# SparkFun_GPS_NEO_M9N.net
KiCad netlist of a schematic drawn in EAGLE
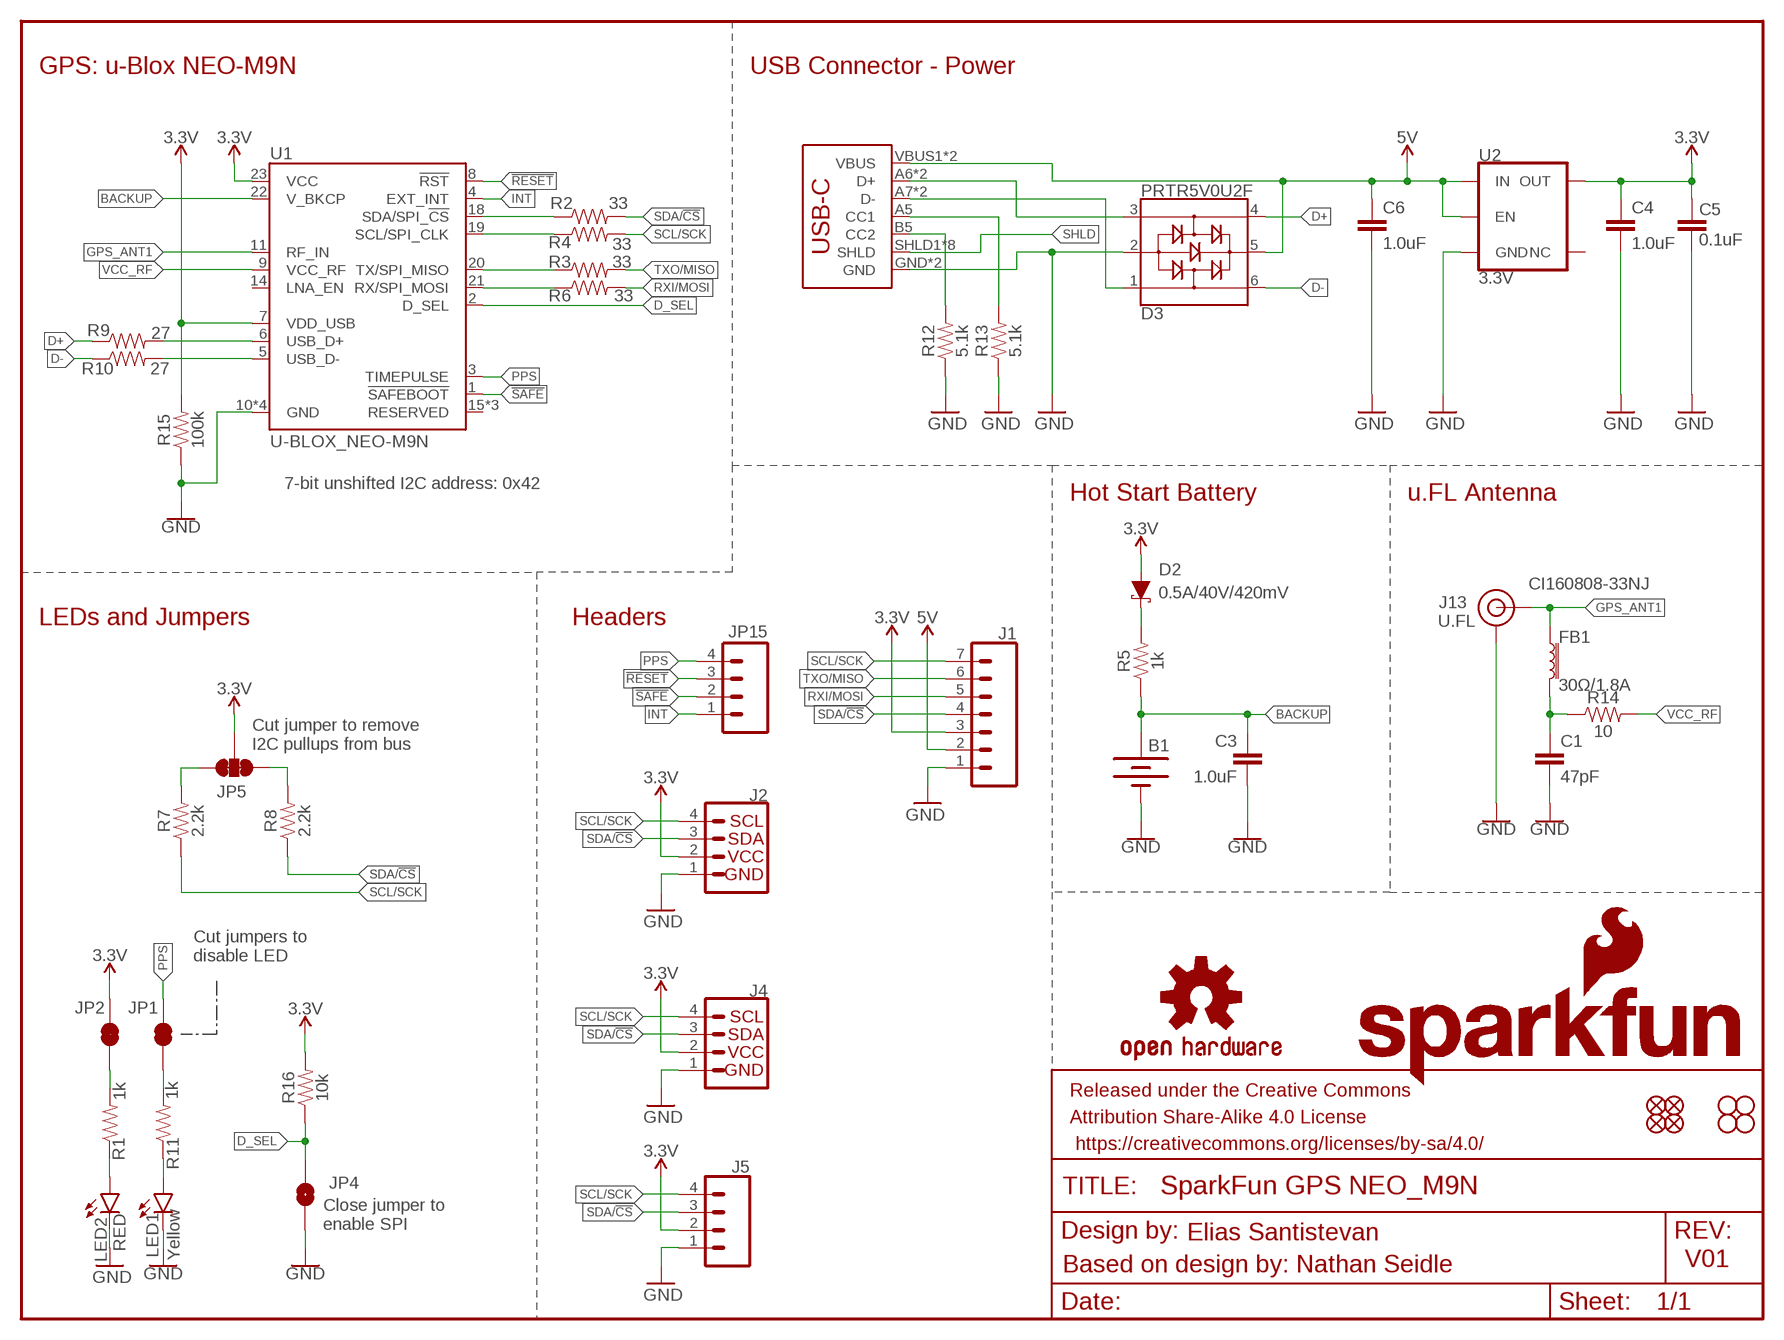
[diagram p0: schematic, sheet 1]

(export (version "E")
  (design (tool "Eeschema 10.0.6"))
  (components
    (comp (ref "B1")
      (value "6.8MM_COIN_CELL")
      (footprint "eagle-import:ML414H_IV01E")
      (libsource (lib "eagle-import") (part "ML414H_IV01E_BATTERY"))
    )
    (comp (ref "C1")
      (value "47pF")
      (footprint "eagle-import:0603")
      (libsource (lib "eagle-import") (part "47PF-0603-50V-5%"))
    )
    (comp (ref "C3")
      (value "1.0uF")
      (footprint "eagle-import:0603")
      (libsource (lib "eagle-import") (part "1.0UF-0603-16V-10%"))
    )
    (comp (ref "C4")
      (value "1.0uF")
      (footprint "eagle-import:0603")
      (libsource (lib "eagle-import") (part "1.0UF-0603-16V-10%"))
    )
    (comp (ref "C5")
      (value "0.1uF")
      (footprint "eagle-import:0603")
      (libsource (lib "eagle-import") (part "0.1UF-0603-25V-(+80/-20%)"))
    )
    (comp (ref "C6")
      (value "1.0uF")
      (footprint "eagle-import:0603")
      (libsource (lib "eagle-import") (part "1.0UF-0603-16V-10%"))
    )
    (comp (ref "D2")
      (value "0.5A/40V/420mV")
      (footprint "eagle-import:SOD-323")
      (libsource (lib "eagle-import") (part "DIODE-SCHOTTKY-PMEG4005EJ"))
    )
    (comp (ref "D3")
      (value "PRTR5V0U2F")
      (footprint "eagle-import:SOT886")
      (libsource (lib "eagle-import") (part "PRTR5V0U2F"))
    )
    (comp (ref "FB1")
      (value "30Ω/1.8A")
      (footprint "eagle-import:0603")
      (libsource (lib "eagle-import") (part "FERRITE_BEAD-0603"))
    )
    (comp (ref "FRAME1")
      (value "FRAME-LETTER")
      (footprint "eagle-import:CREATIVE_COMMONS")
      (libsource (lib "eagle-import") (part "FRAME-LETTER"))
    )
    (comp (ref "J1")
      (value "CONN_07NO_SILK")
      (footprint "eagle-import:1X07_NO_SILK")
      (libsource (lib "eagle-import") (part "CONN_07NO_SILK"))
    )
    (comp (ref "J2")
      (value "Qwiic Right Angle")
      (footprint "eagle-import:JST04_1MM_RA")
      (libsource (lib "eagle-import") (part "I2C_STANDARDQWIIC"))
    )
    (comp (ref "J3")
      (value "USB_C2-LAYER")
      (footprint "eagle-import:USB-C-16P")
      (libsource (lib "eagle-import") (part "USB_C2-LAYER"))
    )
    (comp (ref "J4")
      (value "Qwiic Right Angle")
      (footprint "eagle-import:JST04_1MM_RA")
      (libsource (lib "eagle-import") (part "I2C_STANDARDQWIIC"))
    )
    (comp (ref "J5")
      (value "CONN_041X04_NO_SILK")
      (footprint "eagle-import:1X04_NO_SILK")
      (libsource (lib "eagle-import") (part "CONN_041X04_NO_SILK"))
    )
    (comp (ref "J13")
      (value "U.FL")
      (footprint "eagle-import:U.FL")
      (libsource (lib "eagle-import") (part "U.FL2PIN"))
    )
    (comp (ref "JP1")
      (value "JUMPER-SMT_2_NC_TRACE_SILK")
      (footprint "eagle-import:SMT-JUMPER_2_NC_TRACE_SILK")
      (libsource (lib "eagle-import") (part "JUMPER-SMT_2_NC_TRACE_SILK"))
    )
    (comp (ref "JP2")
      (value "JUMPER-SMT_2_NC_TRACE_SILK")
      (footprint "eagle-import:SMT-JUMPER_2_NC_TRACE_SILK")
      (libsource (lib "eagle-import") (part "JUMPER-SMT_2_NC_TRACE_SILK"))
    )
    (comp (ref "JP4")
      (value "JUMPER-SMT_2_NO_SILK")
      (footprint "eagle-import:SMT-JUMPER_2_NO_SILK")
      (libsource (lib "eagle-import") (part "JUMPER-SMT_2_NO_SILK"))
    )
    (comp (ref "JP5")
      (value "JUMPER-SMT_3_2-NC_TRACE_SILK")
      (footprint "eagle-import:SMT-JUMPER_3_2-NC_TRACE_SILK")
      (libsource (lib "eagle-import") (part "JUMPER-SMT_3_2-NC_TRACE_SILK"))
    )
    (comp (ref "JP15")
      (value "CONN_041X04_NO_SILK")
      (footprint "eagle-import:1X04_NO_SILK")
      (libsource (lib "eagle-import") (part "CONN_041X04_NO_SILK"))
    )
    (comp (ref "JP21")
      (value "FIDUCIALUFIDUCIAL")
      (footprint "eagle-import:MICRO-FIDUCIAL")
      (libsource (lib "eagle-import") (part "FIDUCIALUFIDUCIAL"))
    )
    (comp (ref "JP31")
      (value "STAND-OFF")
      (footprint "eagle-import:STAND-OFF")
      (libsource (lib "eagle-import") (part "STAND-OFF"))
    )
    (comp (ref "JP41")
      (value "STAND-OFF")
      (footprint "eagle-import:STAND-OFF")
      (libsource (lib "eagle-import") (part "STAND-OFF"))
    )
    (comp (ref "JP61")
      (value "FIDUCIALUFIDUCIAL")
      (footprint "eagle-import:MICRO-FIDUCIAL")
      (libsource (lib "eagle-import") (part "FIDUCIALUFIDUCIAL"))
    )
    (comp (ref "JP71")
      (value "FIDUCIALUFIDUCIAL")
      (footprint "eagle-import:MICRO-FIDUCIAL")
      (libsource (lib "eagle-import") (part "FIDUCIALUFIDUCIAL"))
    )
    (comp (ref "JP81")
      (value "FIDUCIALUFIDUCIAL")
      (footprint "eagle-import:MICRO-FIDUCIAL")
      (libsource (lib "eagle-import") (part "FIDUCIALUFIDUCIAL"))
    )
    (comp (ref "JP91")
      (value "STAND-OFF")
      (footprint "eagle-import:STAND-OFF")
      (libsource (lib "eagle-import") (part "STAND-OFF"))
    )
    (comp (ref "JP101")
      (value "STAND-OFF")
      (footprint "eagle-import:STAND-OFF")
      (libsource (lib "eagle-import") (part "STAND-OFF"))
    )
    (comp (ref "LED1")
      (value "Yellow")
      (footprint "eagle-import:LED-0603")
      (libsource (lib "eagle-import") (part "LED-YELLOW0603"))
    )
    (comp (ref "LED2")
      (value "RED")
      (footprint "eagle-import:LED-0603")
      (libsource (lib "eagle-import") (part "LED-RED0603"))
    )
    (comp (ref "LOGO1")
      (value "OSHW-LOGOMINI")
      (footprint "eagle-import:OSHW-LOGO-MINI")
      (libsource (lib "eagle-import") (part "OSHW-LOGOMINI"))
    )
    (comp (ref "LOGO2")
      (value "SFE_LOGO_NAME_FLAME.1_INCH")
      (footprint "eagle-import:SFE_LOGO_NAME_FLAME_.1")
      (libsource (lib "eagle-import") (part "SFE_LOGO_NAME_FLAME.1_INCH"))
    )
    (comp (ref "R1")
      (value "1k")
      (footprint "eagle-import:0603")
      (libsource (lib "eagle-import") (part "1KOHM-0603-1/10W-1%"))
    )
    (comp (ref "R2")
      (value "33")
      (footprint "eagle-import:0603")
      (libsource (lib "eagle-import") (part "33OHM-0603-1/10W-1%"))
    )
    (comp (ref "R3")
      (value "33")
      (footprint "eagle-import:0603")
      (libsource (lib "eagle-import") (part "33OHM-0603-1/10W-1%"))
    )
    (comp (ref "R4")
      (value "33")
      (footprint "eagle-import:0603")
      (libsource (lib "eagle-import") (part "33OHM-0603-1/10W-1%"))
    )
    (comp (ref "R5")
      (value "1k")
      (footprint "eagle-import:0603")
      (libsource (lib "eagle-import") (part "1KOHM-0603-1/10W-1%"))
    )
    (comp (ref "R6")
      (value "33")
      (footprint "eagle-import:0603")
      (libsource (lib "eagle-import") (part "33OHM-0603-1/10W-1%"))
    )
    (comp (ref "R7")
      (value "2.2k")
      (footprint "eagle-import:0603")
      (libsource (lib "eagle-import") (part "2.2KOHM-0603-1/10W-1%"))
    )
    (comp (ref "R8")
      (value "2.2k")
      (footprint "eagle-import:0603")
      (libsource (lib "eagle-import") (part "2.2KOHM-0603-1/10W-1%"))
    )
    (comp (ref "R9")
      (value "27")
      (footprint "eagle-import:0603")
      (libsource (lib "eagle-import") (part "27OHM-0603-1/10W-1%"))
    )
    (comp (ref "R10")
      (value "27")
      (footprint "eagle-import:0603")
      (libsource (lib "eagle-import") (part "27OHM-0603-1/10W-1%"))
    )
    (comp (ref "R11")
      (value "1k")
      (footprint "eagle-import:0603")
      (libsource (lib "eagle-import") (part "1KOHM-0603-1/10W-1%"))
    )
    (comp (ref "R12")
      (value "5.1k")
      (footprint "eagle-import:0402")
      (libsource (lib "eagle-import") (part "5.1KOHM-0402-1/16W-1%"))
    )
    (comp (ref "R13")
      (value "5.1k")
      (footprint "eagle-import:0402")
      (libsource (lib "eagle-import") (part "5.1KOHM-0402-1/16W-1%"))
    )
    (comp (ref "R14")
      (value "10")
      (footprint "eagle-import:0603")
      (libsource (lib "eagle-import") (part "10OHM-0603-1/10W-1%"))
    )
    (comp (ref "R15")
      (value "100k")
      (footprint "eagle-import:0603")
      (libsource (lib "eagle-import") (part "100KOHM-0603-1/10W-1%"))
    )
    (comp (ref "R16")
      (value "10k")
      (footprint "eagle-import:0402")
      (libsource (lib "eagle-import") (part "10KOHM-0402-1/16W-1%"))
    )
    (comp (ref "U1")
      (value "U-BLOX_NEO-M9N")
      (footprint "eagle-import:NEO-M9N")
      (libsource (lib "eagle-import") (part "U-BLOX_NEO-M9N"))
    )
    (comp (ref "U2")
      (value "3.3V")
      (footprint "eagle-import:SOT23-5")
      (libsource (lib "eagle-import") (part "V_REG_AP2112K-3.3V"))
    )
  )
  (nets
    (net (code "1") (name "/SDA{slash}~{CS}") (class "Default")
      (node (ref "J1") (pin "4") (pinfunction "4_4") (pintype "passive"))
      (node (ref "J2") (pin "3") (pinfunction "3_3") (pintype "passive"))
      (node (ref "J4") (pin "3") (pinfunction "3_3") (pintype "passive"))
      (node (ref "J5") (pin "3") (pinfunction "3_3") (pintype "passive"))
      (node (ref "R2") (pin "2") (pinfunction "2_2") (pintype "passive"))
      (node (ref "R8") (pin "1") (pinfunction "1_1") (pintype "passive"))
    )
    (net (code "2") (name "/~{RESET}") (class "Default")
      (node (ref "JP15") (pin "3") (pinfunction "3_3") (pintype "passive"))
      (node (ref "U1") (pin "8") (pinfunction "~{RST}_8") (pintype "bidirectional"))
    )
    (net (code "3") (name "/~{SAFE}") (class "Default")
      (node (ref "JP15") (pin "2") (pinfunction "2_2") (pintype "passive"))
      (node (ref "U1") (pin "1") (pinfunction "~{SAFEBOOT}_1") (pintype "bidirectional"))
    )
    (net (code "4") (name "3.3V") (class "Default")
      (node (ref "C4") (pin "1") (pinfunction "1_1") (pintype "passive"))
      (node (ref "C5") (pin "2") (pinfunction "2_2") (pintype "passive"))
      (node (ref "D2") (pin "A") (pinfunction "A_A") (pintype "passive"))
      (node (ref "J1") (pin "3") (pinfunction "3_3") (pintype "passive"))
      (node (ref "J2") (pin "2") (pinfunction "2_2") (pintype "power_in"))
      (node (ref "J4") (pin "2") (pinfunction "2_2") (pintype "power_in"))
      (node (ref "J5") (pin "2") (pinfunction "2_2") (pintype "passive"))
      (node (ref "JP2") (pin "2") (pinfunction "2_2") (pintype "passive"))
      (node (ref "JP5") (pin "2") (pinfunction "2_2") (pintype "passive"))
      (node (ref "R15") (pin "2") (pinfunction "2_2") (pintype "passive"))
      (node (ref "R16") (pin "2") (pinfunction "2_2") (pintype "passive"))
      (node (ref "U1") (pin "23") (pinfunction "VCC_23") (pintype "bidirectional"))
      (node (ref "U1") (pin "7") (pinfunction "VDD_USB_7") (pintype "bidirectional"))
      (node (ref "U2") (pin "5") (pinfunction "OUT_5") (pintype "passive"))
    )
    (net (code "5") (name "5V") (class "Default")
      (node (ref "C6") (pin "1") (pinfunction "1_1") (pintype "passive"))
      (node (ref "D3") (pin "5") (pinfunction "5_5") (pintype "bidirectional"))
      (node (ref "J1") (pin "2") (pinfunction "2_2") (pintype "passive"))
      (node (ref "J3") (pin "VBUS1") (pinfunction "VBUS_VBUS1") (pintype "bidirectional"))
      (node (ref "J3") (pin "VBUS2") (pinfunction "VBUS_VBUS2") (pintype "bidirectional"))
      (node (ref "U2") (pin "1") (pinfunction "IN_1") (pintype "input"))
      (node (ref "U2") (pin "3") (pinfunction "EN_3") (pintype "input"))
    )
    (net (code "6") (name "BACKUP") (class "Default")
      (node (ref "B1") (pin "+") (pinfunction "+_+") (pintype "power_in"))
      (node (ref "C3") (pin "1") (pinfunction "1_1") (pintype "passive"))
      (node (ref "R5") (pin "1") (pinfunction "1_1") (pintype "passive"))
      (node (ref "U1") (pin "22") (pinfunction "V_BKCP_22") (pintype "bidirectional"))
    )
    (net (code "7") (name "D+") (class "Default")
      (node (ref "D3") (pin "4") (pinfunction "4_4") (pintype "bidirectional"))
      (node (ref "R9") (pin "1") (pinfunction "1_1") (pintype "passive"))
    )
    (net (code "8") (name "D-") (class "Default")
      (node (ref "D3") (pin "6") (pinfunction "6_6") (pintype "bidirectional"))
      (node (ref "R10") (pin "1") (pinfunction "1_1") (pintype "passive"))
    )
    (net (code "9") (name "D_SEL") (class "Default")
      (node (ref "JP4") (pin "2") (pinfunction "2_2") (pintype "passive"))
      (node (ref "R16") (pin "1") (pinfunction "1_1") (pintype "passive"))
      (node (ref "U1") (pin "2") (pinfunction "D_SEL_2") (pintype "bidirectional"))
    )
    (net (code "10") (name "GND") (class "Default")
      (node (ref "B1") (pin "-") (pinfunction "-_-") (pintype "power_in"))
      (node (ref "C1") (pin "2") (pinfunction "2_2") (pintype "passive"))
      (node (ref "C3") (pin "2") (pinfunction "2_2") (pintype "passive"))
      (node (ref "C4") (pin "2") (pinfunction "2_2") (pintype "passive"))
      (node (ref "C5") (pin "1") (pinfunction "1_1") (pintype "passive"))
      (node (ref "C6") (pin "2") (pinfunction "2_2") (pintype "passive"))
      (node (ref "D3") (pin "2") (pinfunction "2_2") (pintype "bidirectional"))
      (node (ref "J1") (pin "1") (pinfunction "1_1") (pintype "passive"))
      (node (ref "J13") (pin "1") (pinfunction "GND_1") (pintype "bidirectional"))
      (node (ref "J13") (pin "2") (pinfunction "GND_2") (pintype "bidirectional"))
      (node (ref "J2") (pin "1") (pinfunction "1_1") (pintype "power_in"))
      (node (ref "J3") (pin "GND") (pinfunction "GND_GND") (pintype "bidirectional"))
      (node (ref "J3") (pin "GND2") (pinfunction "GND_GND2") (pintype "bidirectional"))
      (node (ref "J4") (pin "1") (pinfunction "1_1") (pintype "power_in"))
      (node (ref "J5") (pin "1") (pinfunction "1_1") (pintype "passive"))
      (node (ref "JP4") (pin "1") (pinfunction "1_1") (pintype "passive"))
      (node (ref "LED1") (pin "C") (pinfunction "C_C") (pintype "passive"))
      (node (ref "LED2") (pin "C") (pinfunction "C_C") (pintype "passive"))
      (node (ref "R12") (pin "1") (pinfunction "1_1") (pintype "passive"))
      (node (ref "R13") (pin "1") (pinfunction "1_1") (pintype "passive"))
      (node (ref "R15") (pin "1") (pinfunction "1_1") (pintype "passive"))
      (node (ref "U1") (pin "10") (pinfunction "GND_10") (pintype "bidirectional"))
      (node (ref "U1") (pin "12") (pinfunction "GND_12") (pintype "bidirectional"))
      (node (ref "U1") (pin "13") (pinfunction "GND_13") (pintype "bidirectional"))
      (node (ref "U1") (pin "24") (pinfunction "GND_24") (pintype "bidirectional"))
      (node (ref "U2") (pin "2") (pinfunction "GND_2") (pintype "input"))
    )
    (net (code "11") (name "GPS_ANT1") (class "Default")
      (node (ref "FB1") (pin "1") (pinfunction "1_1") (pintype "passive"))
      (node (ref "J13") (pin "FEED") (pinfunction "SIGNAL_FEED") (pintype "bidirectional"))
      (node (ref "U1") (pin "11") (pinfunction "RF_IN_11") (pintype "bidirectional"))
    )
    (net (code "12") (name "INT") (class "Default")
      (node (ref "JP15") (pin "1") (pinfunction "1_1") (pintype "passive"))
      (node (ref "U1") (pin "4") (pinfunction "EXT_INT_4") (pintype "bidirectional"))
    )
    (net (code "13") (name "Net-(C1-Pad1)") (class "Default")
      (node (ref "C1") (pin "1") (pinfunction "1_1") (pintype "passive"))
      (node (ref "FB1") (pin "2") (pinfunction "2_2") (pintype "passive"))
      (node (ref "R14") (pin "1") (pinfunction "1_1") (pintype "passive"))
    )
    (net (code "14") (name "Net-(D2-PadC)") (class "Default")
      (node (ref "D2") (pin "C") (pinfunction "C_C") (pintype "passive"))
      (node (ref "R5") (pin "2") (pinfunction "2_2") (pintype "passive"))
    )
    (net (code "15") (name "Net-(D3-Pad1)") (class "Default")
      (node (ref "D3") (pin "1") (pinfunction "1_1") (pintype "bidirectional"))
      (node (ref "J3") (pin "A7") (pinfunction "D-_A7") (pintype "bidirectional"))
      (node (ref "J3") (pin "B7") (pinfunction "D-_B7") (pintype "bidirectional"))
    )
    (net (code "16") (name "Net-(D3-Pad3)") (class "Default")
      (node (ref "D3") (pin "3") (pinfunction "3_3") (pintype "bidirectional"))
      (node (ref "J3") (pin "A6") (pinfunction "D+_A6") (pintype "bidirectional"))
      (node (ref "J3") (pin "B6") (pinfunction "D+_B6") (pintype "bidirectional"))
    )
    (net (code "17") (name "Net-(J3-CC1)") (class "Default")
      (node (ref "J3") (pin "A5") (pinfunction "CC1_A5") (pintype "bidirectional"))
      (node (ref "R13") (pin "2") (pinfunction "2_2") (pintype "passive"))
    )
    (net (code "18") (name "Net-(J3-CC2)") (class "Default")
      (node (ref "J3") (pin "B5") (pinfunction "CC2_B5") (pintype "bidirectional"))
      (node (ref "R12") (pin "2") (pinfunction "2_2") (pintype "passive"))
    )
    (net (code "19") (name "Net-(JP1-Pad1)") (class "Default")
      (node (ref "JP1") (pin "1") (pinfunction "1_1") (pintype "passive"))
      (node (ref "R11") (pin "2") (pinfunction "2_2") (pintype "passive"))
    )
    (net (code "20") (name "Net-(JP2-Pad1)") (class "Default")
      (node (ref "JP2") (pin "1") (pinfunction "1_1") (pintype "passive"))
      (node (ref "R1") (pin "2") (pinfunction "2_2") (pintype "passive"))
    )
    (net (code "21") (name "Net-(JP5-Pad1)") (class "Default")
      (node (ref "JP5") (pin "1") (pinfunction "1_1") (pintype "passive"))
      (node (ref "R8") (pin "2") (pinfunction "2_2") (pintype "passive"))
    )
    (net (code "22") (name "Net-(JP5-Pad3)") (class "Default")
      (node (ref "JP5") (pin "3") (pinfunction "3_3") (pintype "passive"))
      (node (ref "R7") (pin "2") (pinfunction "2_2") (pintype "passive"))
    )
    (net (code "23") (name "Net-(LED1-PadA)") (class "Default")
      (node (ref "LED1") (pin "A") (pinfunction "A_A") (pintype "passive"))
      (node (ref "R11") (pin "1") (pinfunction "1_1") (pintype "passive"))
    )
    (net (code "24") (name "Net-(LED2-PadA)") (class "Default")
      (node (ref "LED2") (pin "A") (pinfunction "A_A") (pintype "passive"))
      (node (ref "R1") (pin "1") (pinfunction "1_1") (pintype "passive"))
    )
    (net (code "25") (name "Net-(U1-RX{slash}SPI_MOSI)") (class "Default")
      (node (ref "R6") (pin "1") (pinfunction "1_1") (pintype "passive"))
      (node (ref "U1") (pin "21") (pinfunction "RX/SPI_MOSI_21") (pintype "bidirectional"))
    )
    (net (code "26") (name "Net-(U1-SCL{slash}SPI_CLK)") (class "Default")
      (node (ref "R4") (pin "1") (pinfunction "1_1") (pintype "passive"))
      (node (ref "U1") (pin "19") (pinfunction "SCL/SPI_CLK_19") (pintype "bidirectional"))
    )
    (net (code "27") (name "Net-(U1-SDA{slash}SPI_~{CS})") (class "Default")
      (node (ref "R2") (pin "1") (pinfunction "1_1") (pintype "passive"))
      (node (ref "U1") (pin "18") (pinfunction "SDA/SPI_~{CS}_18") (pintype "bidirectional"))
    )
    (net (code "28") (name "Net-(U1-TX{slash}SPI_MISO)") (class "Default")
      (node (ref "R3") (pin "1") (pinfunction "1_1") (pintype "passive"))
      (node (ref "U1") (pin "20") (pinfunction "TX/SPI_MISO_20") (pintype "bidirectional"))
    )
    (net (code "29") (name "Net-(U1-USB_D+)") (class "Default")
      (node (ref "R9") (pin "2") (pinfunction "2_2") (pintype "passive"))
      (node (ref "U1") (pin "6") (pinfunction "USB_D+_6") (pintype "bidirectional"))
    )
    (net (code "30") (name "Net-(U1-USB_D-)") (class "Default")
      (node (ref "R10") (pin "2") (pinfunction "2_2") (pintype "passive"))
      (node (ref "U1") (pin "5") (pinfunction "USB_D-_5") (pintype "bidirectional"))
    )
    (net (code "31") (name "PPS") (class "Default")
      (node (ref "JP1") (pin "2") (pinfunction "2_2") (pintype "passive"))
      (node (ref "JP15") (pin "4") (pinfunction "4_4") (pintype "passive"))
      (node (ref "U1") (pin "3") (pinfunction "TIMEPULSE_3") (pintype "bidirectional"))
    )
    (net (code "32") (name "RXI{slash}MOSI") (class "Default")
      (node (ref "J1") (pin "5") (pinfunction "5_5") (pintype "passive"))
      (node (ref "R6") (pin "2") (pinfunction "2_2") (pintype "passive"))
    )
    (net (code "33") (name "SCL{slash}SCK") (class "Default")
      (node (ref "J1") (pin "7") (pinfunction "7_7") (pintype "passive"))
      (node (ref "J2") (pin "4") (pinfunction "4_4") (pintype "passive"))
      (node (ref "J4") (pin "4") (pinfunction "4_4") (pintype "passive"))
      (node (ref "J5") (pin "4") (pinfunction "4_4") (pintype "passive"))
      (node (ref "R4") (pin "2") (pinfunction "2_2") (pintype "passive"))
      (node (ref "R7") (pin "1") (pinfunction "1_1") (pintype "passive"))
    )
    (net (code "34") (name "SHLD") (class "Default")
      (node (ref "J3") (pin "SHLD1") (pinfunction "SHLD_SHLD1") (pintype "bidirectional"))
      (node (ref "J3") (pin "SHLD2") (pinfunction "SHLD_SHLD2") (pintype "bidirectional"))
      (node (ref "J3") (pin "SHLD3") (pinfunction "SHLD_SHLD3") (pintype "bidirectional"))
      (node (ref "J3") (pin "SHLD4") (pinfunction "SHLD_SHLD4") (pintype "bidirectional"))
      (node (ref "J3") (pin "SHLD5") (pinfunction "SHLD_SHLD5") (pintype "bidirectional"))
      (node (ref "J3") (pin "SHLD6") (pinfunction "SHLD_SHLD6") (pintype "bidirectional"))
      (node (ref "J3") (pin "SHLD7") (pinfunction "SHLD_SHLD7") (pintype "bidirectional"))
      (node (ref "J3") (pin "SHLD8") (pinfunction "SHLD_SHLD8") (pintype "bidirectional"))
    )
    (net (code "35") (name "TXO{slash}MISO") (class "Default")
      (node (ref "J1") (pin "6") (pinfunction "6_6") (pintype "passive"))
      (node (ref "R3") (pin "2") (pinfunction "2_2") (pintype "passive"))
    )
    (net (code "36") (name "VCC_RF") (class "Default")
      (node (ref "R14") (pin "2") (pinfunction "2_2") (pintype "passive"))
      (node (ref "U1") (pin "9") (pinfunction "VCC_RF_9") (pintype "bidirectional"))
    )
    (net (code "37") (name "unconnected-(U1-LNA_EN-Pad14)") (class "Default")
      (node (ref "U1") (pin "14") (pinfunction "LNA_EN_14") (pintype "bidirectional"))
    )
    (net (code "38") (name "unconnected-(U1-RESERVED-Pad15)") (class "Default")
      (node (ref "U1") (pin "15") (pinfunction "RESERVED_15") (pintype "no_connect"))
    )
    (net (code "39") (name "unconnected-(U1-RESERVED-Pad16)") (class "Default")
      (node (ref "U1") (pin "16") (pinfunction "RESERVED_16") (pintype "no_connect"))
    )
    (net (code "40") (name "unconnected-(U1-RESERVED-Pad17)") (class "Default")
      (node (ref "U1") (pin "17") (pinfunction "RESERVED_17") (pintype "no_connect"))
    )
    (net (code "41") (name "unconnected-(U2-NC-Pad4)") (class "Default")
      (node (ref "U2") (pin "4") (pinfunction "NC_4") (pintype "no_connect"))
    )
  )
)
